# BrimEff.net
KiCad netlist of a schematic drawn in EAGLE
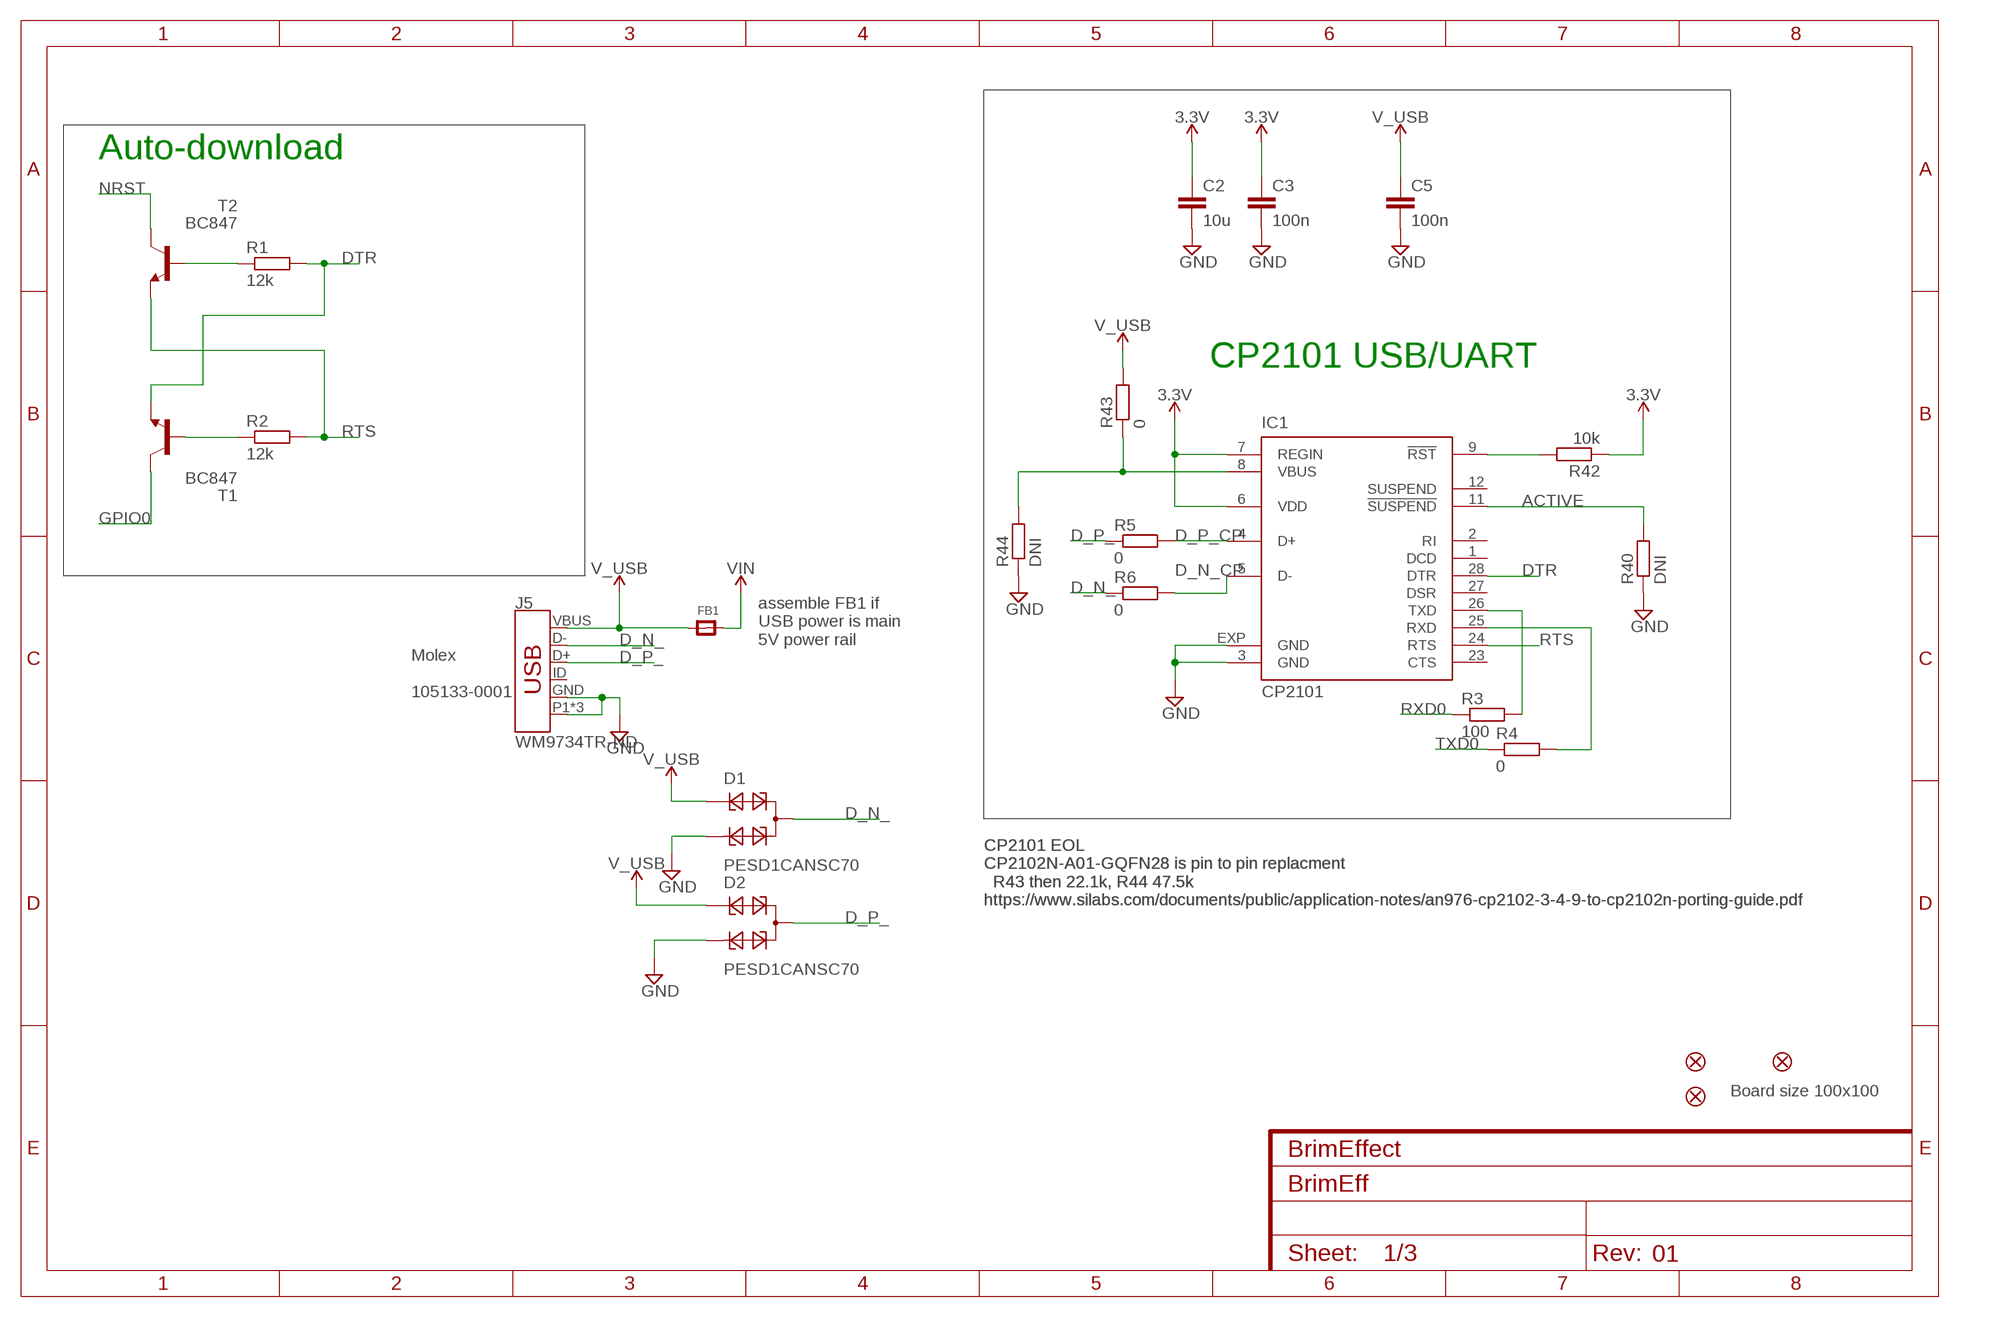
[diagram p0: schematic, sheet 1]
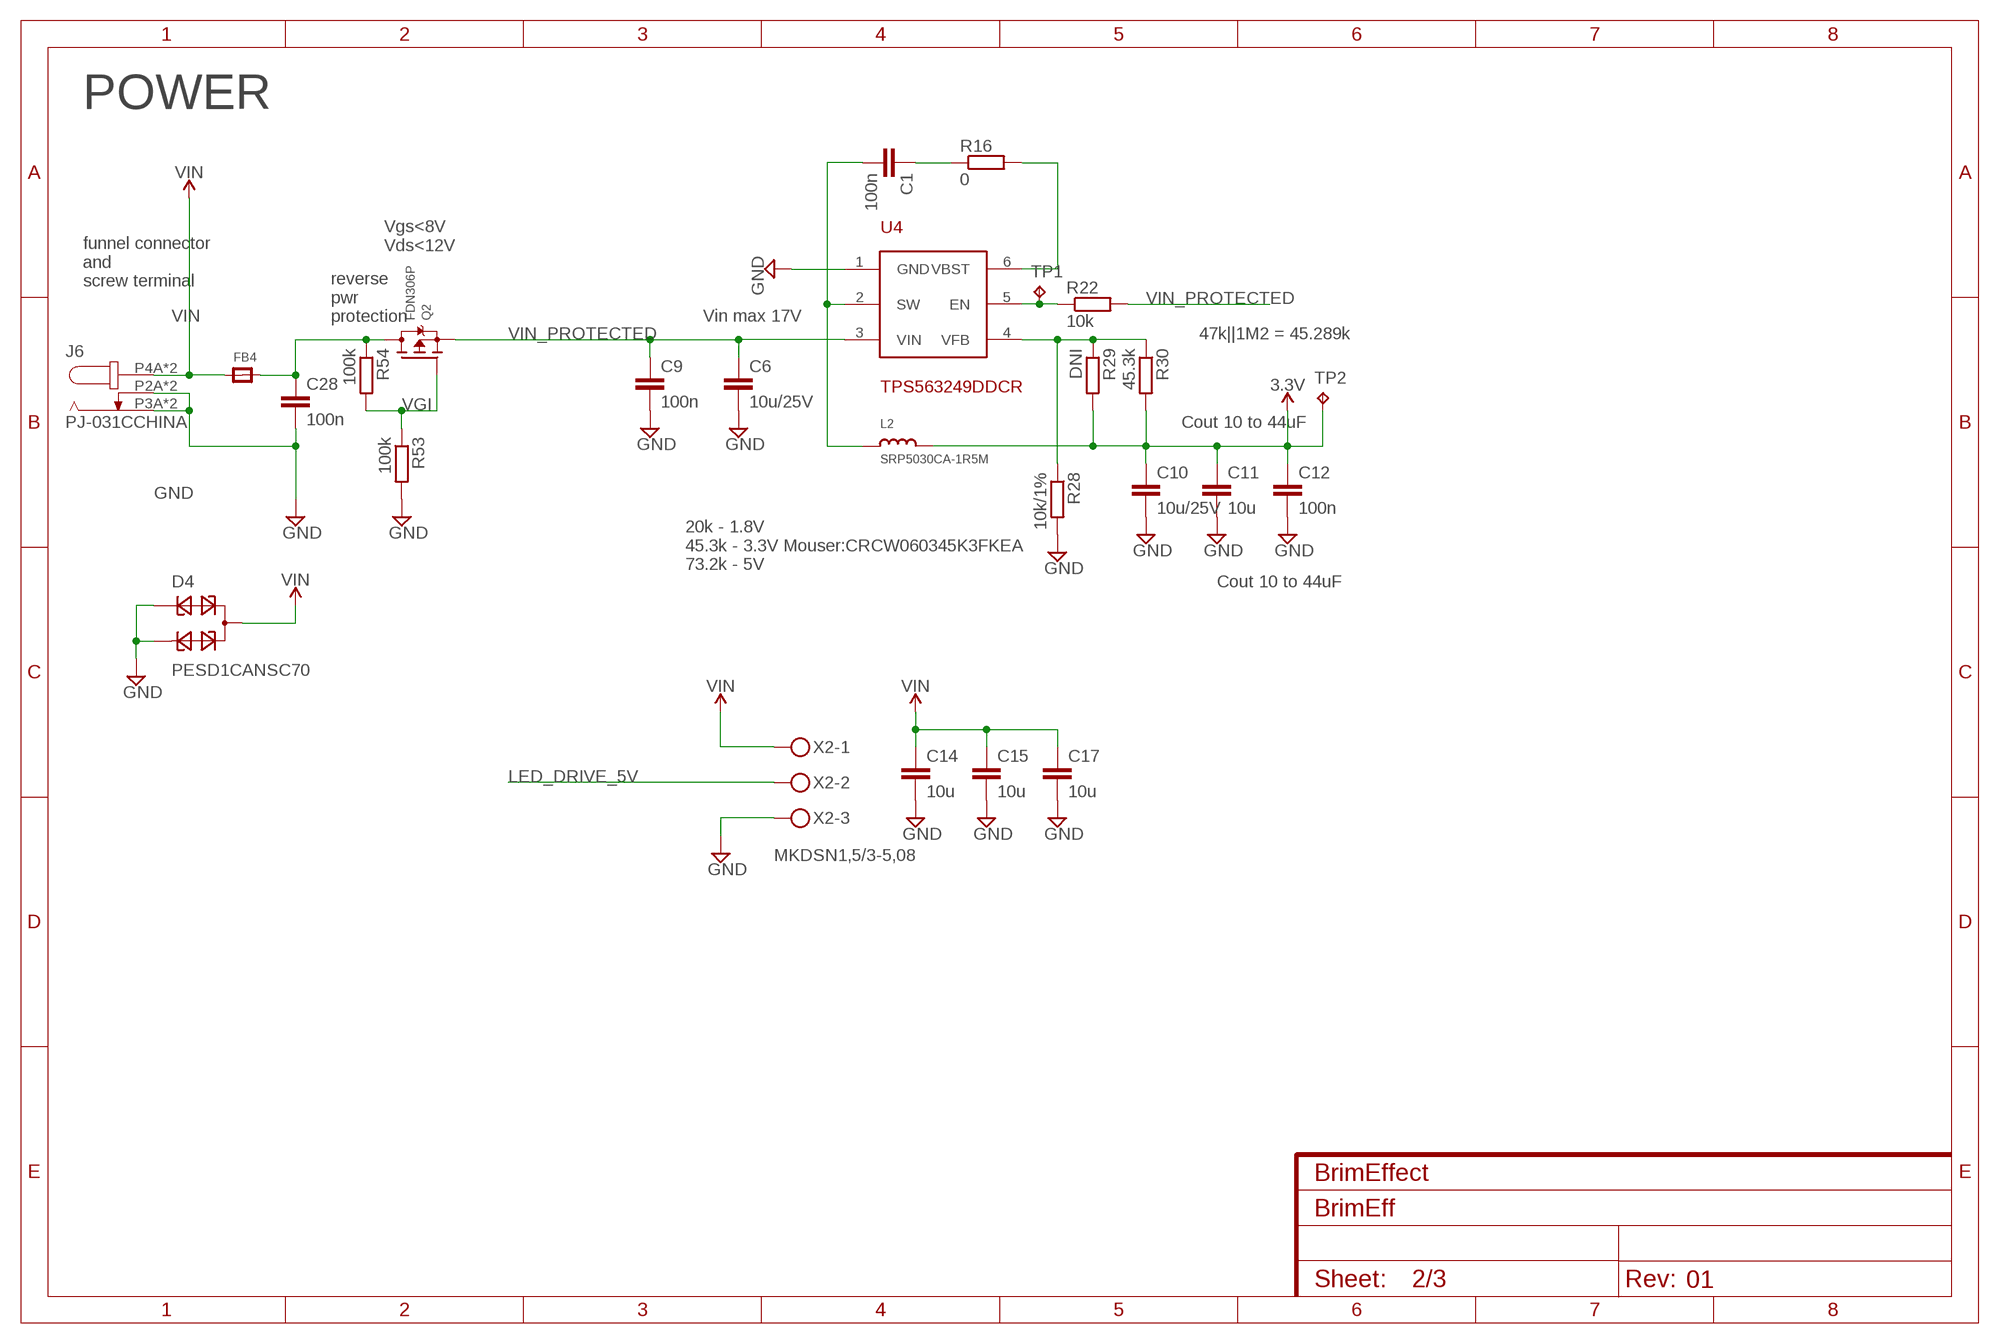
[diagram p1: schematic, sheet 2]
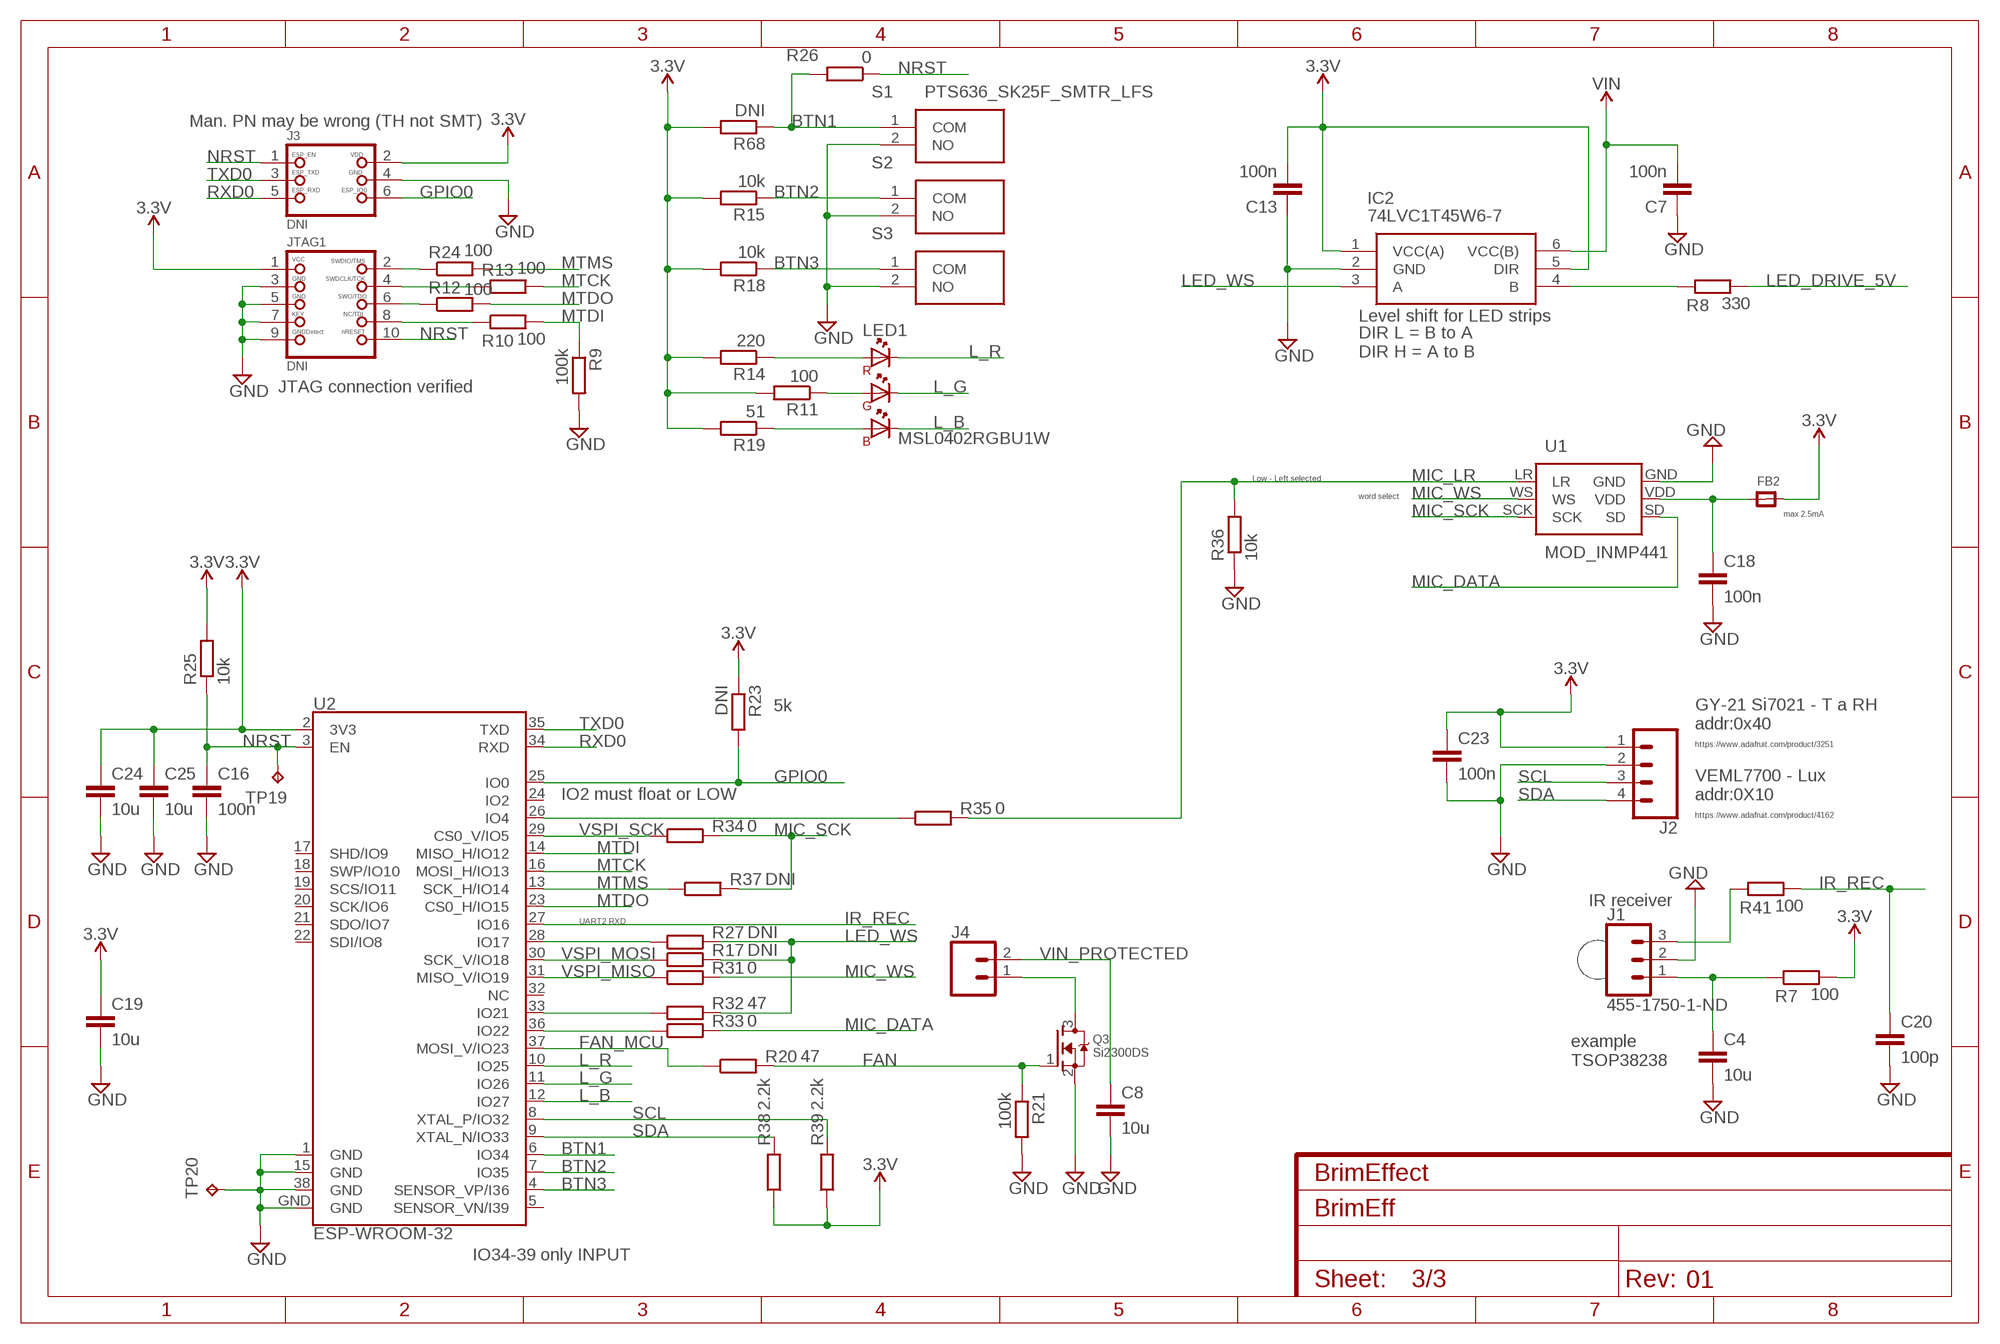
[diagram p2: schematic, sheet 3]

(export (version "E")
  (design (tool "Eeschema 10.0.6"))
  (components
    (comp (ref "C1")
      (value "100n")
      (footprint "eagle-import:C0603K")
      (fields (field (name "PARTNO") "CC0603KRX7R8BB104"))
      (libsource (lib "eagle-import") (part "C-EUC0603K"))
    )
    (comp (ref "C6")
      (value "10u/25V")
      (footprint "eagle-import:C0603K")
      (fields (field (name "PARTNO") "GRM188R61E106KA73J"))
      (libsource (lib "eagle-import") (part "C-EUC0603K"))
    )
    (comp (ref "C9")
      (value "100n")
      (footprint "eagle-import:C0603K")
      (fields (field (name "PARTNO") "CC0603KRX7R8BB104"))
      (libsource (lib "eagle-import") (part "C-EUC0603K"))
    )
    (comp (ref "C10")
      (value "10u/25V")
      (footprint "eagle-import:C0603K")
      (fields (field (name "PARTNO") "GRM188R61E106KA73J"))
      (libsource (lib "eagle-import") (part "C-EUC0603K"))
    )
    (comp (ref "C11")
      (value "10u")
      (footprint "eagle-import:C0603K")
      (fields (field (name "PARTNO") "GRM188R61A106KE69J"))
      (libsource (lib "eagle-import") (part "C-EUC0603K"))
    )
    (comp (ref "C12")
      (value "100n")
      (footprint "eagle-import:C0603K")
      (fields (field (name "PARTNO") "CC0603KRX7R8BB104"))
      (libsource (lib "eagle-import") (part "C-EUC0603K"))
    )
    (comp (ref "C14")
      (value "10u")
      (footprint "eagle-import:C0603K")
      (fields (field (name "PARTNO") "GRM188R61A106KE69J"))
      (libsource (lib "eagle-import") (part "C-EUC0603K"))
    )
    (comp (ref "C15")
      (value "10u")
      (footprint "eagle-import:C0603K")
      (fields (field (name "PARTNO") "GRM188R61A106KE69J"))
      (libsource (lib "eagle-import") (part "C-EUC0603K"))
    )
    (comp (ref "C17")
      (value "10u")
      (footprint "eagle-import:C0603K")
      (fields (field (name "PARTNO") "GRM188R61A106KE69J"))
      (libsource (lib "eagle-import") (part "C-EUC0603K"))
    )
    (comp (ref "C28")
      (value "100n")
      (footprint "eagle-import:C0603K")
      (fields (field (name "PARTNO") "CC0603KRX7R8BB104"))
      (libsource (lib "eagle-import") (part "C-EUC0603K"))
    )
    (comp (ref "D4")
      (value "PESD1CANSC70")
      (footprint "eagle-import:SOT323-R")
      (fields (field (name "PARTNO") "PESD1CAN-UX"))
      (libsource (lib "eagle-import") (part "PESD1CANSC70"))
    )
    (comp (ref "FB4")
      (value "FERRITE")
      (footprint "eagle-import:0603")
      (fields (field (name "PARTNO") "BLM18PG121SN1D"))
      (libsource (lib "eagle-import") (part "FERRITE"))
    )
    (comp (ref "J6")
      (value "PJ-031CCHINA")
      (footprint "eagle-import:DC-005_5.5X2.1MM_JACK")
      (libsource (lib "eagle-import") (part "PJ-031CCHINA"))
    )
    (comp (ref "L2")
      (value "SRP5030CA-1R5M")
      (footprint "eagle-import:SRP5030CA")
      (fields (field (name "PARTNO") "SRP5030CA-1R5M "))
      (libsource (lib "eagle-import") (part "SRP5030CA-1R5M"))
    )
    (comp (ref "Q2")
      (value "FDN306P")
      (footprint "eagle-import:SOT23-WIDE")
      (libsource (lib "eagle-import") (part "MOSFET-PWIDE"))
    )
    (comp (ref "R16")
      (value "0")
      (footprint "eagle-import:R0603")
      (fields (field (name "PARTNO") "CRCW06030000Z0EAC"))
      (libsource (lib "eagle-import") (part "R-EU_R0603"))
    )
    (comp (ref "R22")
      (value "10k")
      (footprint "eagle-import:R0603")
      (fields (field (name "PARTNO") "CRCW060310K0JNEAC"))
      (libsource (lib "eagle-import") (part "R-EU_R0603"))
    )
    (comp (ref "R28")
      (value "10k/1%")
      (footprint "eagle-import:R0603")
      (fields (field (name "PARTNO") "RN73R1JTTD1002D25"))
      (libsource (lib "eagle-import") (part "R-EU_R0603"))
    )
    (comp (ref "R29")
      (value "DNI")
      (footprint "eagle-import:R0603")
      (libsource (lib "eagle-import") (part "R-EU_R0603"))
    )
    (comp (ref "R30")
      (value "45.3k")
      (footprint "eagle-import:R0603")
      (fields (field (name "PARTNO") "ERJ-PB3D4532V"))
      (libsource (lib "eagle-import") (part "R-EU_R0603"))
    )
    (comp (ref "R53")
      (value "100k")
      (footprint "eagle-import:R0603")
      (fields (field (name "PARTNO") "CRCW0603100KFKEAC"))
      (libsource (lib "eagle-import") (part "R-EU_R0603"))
    )
    (comp (ref "R54")
      (value "100k")
      (footprint "eagle-import:R0603")
      (fields (field (name "PARTNO") "CRCW0603100KFKEAC"))
      (libsource (lib "eagle-import") (part "R-EU_R0603"))
    )
    (comp (ref "TP1")
      (value "TPTP10R")
      (footprint "eagle-import:TP10R")
      (libsource (lib "eagle-import") (part "TPTP10R"))
    )
    (comp (ref "TP2")
      (value "TPTP10R")
      (footprint "eagle-import:TP10R")
      (libsource (lib "eagle-import") (part "TPTP10R"))
    )
    (comp (ref "U4")
      (value "TPS563249DDCR")
      (footprint "eagle-import:SOT23-6")
      (fields (field (name "PARTNO") "TPS563249DDCR "))
      (libsource (lib "eagle-import") (part "TPS5632149DDCR"))
    )
    (comp (ref "X2")
      (value "MKDSN1,5/3-5,08")
      (footprint "eagle-import:MKDSN1,5_3-5,08")
      (libsource (lib "eagle-import") (part "MKDSN1,5/3-5,08"))
    )
    (comp (ref "C4")
      (value "10u")
      (footprint "eagle-import:C0603K")
      (fields (field (name "PARTNO") "GRM188R61A106KE69J"))
      (libsource (lib "eagle-import") (part "C-EUC0603K"))
    )
    (comp (ref "C7")
      (value "100n")
      (footprint "eagle-import:C0603K")
      (fields (field (name "PARTNO") "CC0603KRX7R8BB104"))
      (libsource (lib "eagle-import") (part "C-EUC0603K"))
    )
    (comp (ref "C8")
      (value "10u")
      (footprint "eagle-import:C0603K")
      (fields (field (name "PARTNO") "GRM188R61A106KE69J"))
      (libsource (lib "eagle-import") (part "C-EUC0603K"))
    )
    (comp (ref "C13")
      (value "100n")
      (footprint "eagle-import:C0603K")
      (fields (field (name "PARTNO") "CC0603KRX7R8BB104"))
      (libsource (lib "eagle-import") (part "C-EUC0603K"))
    )
    (comp (ref "C16")
      (value "100n")
      (footprint "eagle-import:C0603K")
      (fields (field (name "PARTNO") "CC0603KRX7R8BB104"))
      (libsource (lib "eagle-import") (part "C-EUC0603K"))
    )
    (comp (ref "C18")
      (value "100n")
      (footprint "eagle-import:C0603K")
      (fields (field (name "PARTNO") "CC0603KRX7R8BB104"))
      (libsource (lib "eagle-import") (part "C-EUC0603K"))
    )
    (comp (ref "C19")
      (value "10u")
      (footprint "eagle-import:C0603K")
      (fields (field (name "PARTNO") "GRM188R61A106KE69J"))
      (libsource (lib "eagle-import") (part "C-EUC0603K"))
    )
    (comp (ref "C20")
      (value "100p")
      (footprint "eagle-import:C0603K")
      (fields (field (name "PARTNO") "GRM188R61A106KE69J"))
      (libsource (lib "eagle-import") (part "C-EUC0603K"))
    )
    (comp (ref "C23")
      (value "100n")
      (footprint "eagle-import:C0603K")
      (fields (field (name "PARTNO") "CC0603KRX7R8BB104"))
      (libsource (lib "eagle-import") (part "C-EUC0603K"))
    )
    (comp (ref "C24")
      (value "10u")
      (footprint "eagle-import:C0603K")
      (fields (field (name "PARTNO") "GRM188R61A106KE69J"))
      (libsource (lib "eagle-import") (part "C-EUC0603K"))
    )
    (comp (ref "C25")
      (value "10u")
      (footprint "eagle-import:C0603K")
      (fields (field (name "PARTNO") "GRM188R61A106KE69J"))
      (libsource (lib "eagle-import") (part "C-EUC0603K"))
    )
    (comp (ref "FB2")
      (value "FERRITE")
      (footprint "eagle-import:0603")
      (fields (field (name "PARTNO") "BLM18PG121SN1D"))
      (libsource (lib "eagle-import") (part "FERRITE"))
    )
    (comp (ref "IC2")
      (value "74LVC1T45W6-7")
      (footprint "eagle-import:SOT95P285X140-6N")
      (fields (field (name "MOUSER_PART_NUMBER") "621-74LVC1T45W6-7"))
      (libsource (lib "eagle-import") (part "74LVC1T45W6-7"))
    )
    (comp (ref "J1")
      (value "455-1750-1-ND")
      (footprint "eagle-import:1X03")
      (libsource (lib "eagle-import") (part "CONN_03"))
    )
    (comp (ref "J2")
      (value "CONN_04PTH")
      (footprint "eagle-import:1X04")
      (libsource (lib "eagle-import") (part "CONN_04PTH"))
    )
    (comp (ref "J3")
      (value "DNI")
      (footprint "eagle-import:2X03_1.27MM_SMT")
      (fields (field (name "PARTNO") "HTMS-103-03-T-D-SM"))
      (libsource (lib "eagle-import") (part "HEADER_3X6P_ESPPROG"))
    )
    (comp (ref "J4")
      (value "CONN_02")
      (footprint "eagle-import:1X02")
      (libsource (lib "eagle-import") (part "CONN_02"))
    )
    (comp (ref "JTAG1")
      (value "DNI")
      (footprint "eagle-import:2X05_1.27MM_SMT")
      (fields (field (name "PARTNO") "M50-3600542R"))
      (libsource (lib "eagle-import") (part "JTAG-CORTEXM3"))
    )
    (comp (ref "LED1")
      (value "MSL0402RGBU1W")
      (footprint "eagle-import:MSL0402RGBU1-W")
      (libsource (lib "eagle-import") (part "MSL0402RGBU1W"))
    )
    (comp (ref "Q3")
      (value "Si2300DS")
      (footprint "eagle-import:SOT23")
      (fields (field (name "PARTNO") "SI2300DS-T1-GE3"))
      (libsource (lib "eagle-import") (part "MOSFET-NREFLOW"))
    )
    (comp (ref "R7")
      (value "100")
      (footprint "eagle-import:R0603")
      (fields (field (name "PARTNO") "CRCW0603100RFKEAC"))
      (libsource (lib "eagle-import") (part "R-EU_R0603"))
    )
    (comp (ref "R8")
      (value "330")
      (footprint "eagle-import:R0603")
      (fields (field (name "PARTNO") "CRCW0603100RFKEAC"))
      (libsource (lib "eagle-import") (part "R-EU_R0603"))
    )
    (comp (ref "R9")
      (value "100k")
      (footprint "eagle-import:R0603")
      (fields (field (name "PARTNO") "CRCW0603100KFKEAC"))
      (libsource (lib "eagle-import") (part "R-EU_R0603"))
    )
    (comp (ref "R10")
      (value "100")
      (footprint "eagle-import:R0603")
      (fields (field (name "PARTNO") "CRCW0603100RFKEAC"))
      (libsource (lib "eagle-import") (part "R-EU_R0603"))
    )
    (comp (ref "R11")
      (value "100")
      (footprint "eagle-import:R0603")
      (fields (field (name "PARTNO") "CRCW0603100RFKEAC"))
      (libsource (lib "eagle-import") (part "R-EU_R0603"))
    )
    (comp (ref "R12")
      (value "100")
      (footprint "eagle-import:R0603")
      (fields (field (name "PARTNO") "CRCW0603100RFKEAC"))
      (libsource (lib "eagle-import") (part "R-EU_R0603"))
    )
    (comp (ref "R13")
      (value "100")
      (footprint "eagle-import:R0603")
      (fields (field (name "PARTNO") "CRCW0603100RFKEAC"))
      (libsource (lib "eagle-import") (part "R-EU_R0603"))
    )
    (comp (ref "R14")
      (value "220")
      (footprint "eagle-import:R0603")
      (fields (field (name "PARTNO") "CRCW0603100RFKEAC"))
      (libsource (lib "eagle-import") (part "R-EU_R0603"))
    )
    (comp (ref "R15")
      (value "10k")
      (footprint "eagle-import:R0603")
      (fields (field (name "PARTNO") "CRCW060310K0JNEAC"))
      (libsource (lib "eagle-import") (part "R-EU_R0603"))
    )
    (comp (ref "R17")
      (value "DNI")
      (footprint "eagle-import:R0603")
      (fields (field (name "PARTNO") "CRCW060347R0FKEAC"))
      (libsource (lib "eagle-import") (part "R-EU_R0603"))
    )
    (comp (ref "R18")
      (value "10k")
      (footprint "eagle-import:R0603")
      (fields (field (name "PARTNO") "CRCW060310K0JNEAC"))
      (libsource (lib "eagle-import") (part "R-EU_R0603"))
    )
    (comp (ref "R19")
      (value "51")
      (footprint "eagle-import:R0603")
      (fields (field (name "PARTNO") "CRCW0603100RFKEAC"))
      (libsource (lib "eagle-import") (part "R-EU_R0603"))
    )
    (comp (ref "R20")
      (value "47")
      (footprint "eagle-import:R0603")
      (fields (field (name "PARTNO") "CRCW060347R0FKEAC"))
      (libsource (lib "eagle-import") (part "R-EU_R0603"))
    )
    (comp (ref "R21")
      (value "100k")
      (footprint "eagle-import:R0603")
      (fields (field (name "PARTNO") "CRCW0603100KFKEAC"))
      (libsource (lib "eagle-import") (part "R-EU_R0603"))
    )
    (comp (ref "R23")
      (value "DNI")
      (footprint "eagle-import:R0603")
      (fields (field (name "PARTNO") "CRCW06030000Z0EAC"))
      (libsource (lib "eagle-import") (part "R-EU_R0603"))
    )
    (comp (ref "R24")
      (value "100")
      (footprint "eagle-import:R0603")
      (fields (field (name "PARTNO") "CRCW0603100RFKEAC"))
      (libsource (lib "eagle-import") (part "R-EU_R0603"))
    )
    (comp (ref "R25")
      (value "10k")
      (footprint "eagle-import:R0603")
      (fields (field (name "PARTNO") "CRCW060310K0JNEAC"))
      (libsource (lib "eagle-import") (part "R-EU_R0603"))
    )
    (comp (ref "R26")
      (value "0")
      (footprint "eagle-import:R0603")
      (fields (field (name "PARTNO") "CRCW060310K0JNEAC"))
      (libsource (lib "eagle-import") (part "R-EU_R0603"))
    )
    (comp (ref "R27")
      (value "DNI")
      (footprint "eagle-import:R0603")
      (fields (field (name "PARTNO") "CRCW060347R0FKEAC"))
      (libsource (lib "eagle-import") (part "R-EU_R0603"))
    )
    (comp (ref "R31")
      (value "0")
      (footprint "eagle-import:R0603")
      (fields (field (name "PARTNO") "CRCW060347R0FKEAC"))
      (libsource (lib "eagle-import") (part "R-EU_R0603"))
    )
    (comp (ref "R32")
      (value "47")
      (footprint "eagle-import:R0603")
      (fields (field (name "PARTNO") "CRCW060347R0FKEAC"))
      (libsource (lib "eagle-import") (part "R-EU_R0603"))
    )
    (comp (ref "R33")
      (value "0")
      (footprint "eagle-import:R0603")
      (fields (field (name "PARTNO") "CRCW060347R0FKEAC"))
      (libsource (lib "eagle-import") (part "R-EU_R0603"))
    )
    (comp (ref "R34")
      (value "0")
      (footprint "eagle-import:R0603")
      (fields (field (name "PARTNO") "CRCW060347R0FKEAC"))
      (libsource (lib "eagle-import") (part "R-EU_R0603"))
    )
    (comp (ref "R35")
      (value "0")
      (footprint "eagle-import:R0603")
      (fields (field (name "PARTNO") "CRCW060347R0FKEAC"))
      (libsource (lib "eagle-import") (part "R-EU_R0603"))
    )
    (comp (ref "R36")
      (value "10k")
      (footprint "eagle-import:R0603")
      (fields (field (name "PARTNO") "CRCW060310K0JNEAC"))
      (libsource (lib "eagle-import") (part "R-EU_R0603"))
    )
    (comp (ref "R37")
      (value "DNI")
      (footprint "eagle-import:R0603")
      (fields (field (name "PARTNO") "CRCW060347R0FKEAC"))
      (libsource (lib "eagle-import") (part "R-EU_R0603"))
    )
    (comp (ref "R38")
      (value "2.2k")
      (footprint "eagle-import:R0603")
      (fields (field (name "PARTNO") "CRCW060347R0FKEAC"))
      (libsource (lib "eagle-import") (part "R-EU_R0603"))
    )
    (comp (ref "R39")
      (value "2.2k")
      (footprint "eagle-import:R0603")
      (fields (field (name "PARTNO") "CRCW060347R0FKEAC"))
      (libsource (lib "eagle-import") (part "R-EU_R0603"))
    )
    (comp (ref "R41")
      (value "100")
      (footprint "eagle-import:R0603")
      (fields (field (name "PARTNO") "CRCW0603100RFKEAC"))
      (libsource (lib "eagle-import") (part "R-EU_R0603"))
    )
    (comp (ref "R68")
      (value "DNI")
      (footprint "eagle-import:R0603")
      (fields (field (name "PARTNO") "CRCW060310K0JNEAC"))
      (libsource (lib "eagle-import") (part "R-EU_R0603"))
    )
    (comp (ref "S1")
      (value "PTS636_SK25F_SMTR_LFS")
      (footprint "eagle-import:PTS636SK25FSMTRLFS")
      (fields
        (field (name "MANUFACTURER_PART_NUMBER") "PTS636 SK25F SMTR LFS")
        (field (name "MOUSER_PART_NUMBER") "611-PTS636SK25FSMTRL")
      )
      (libsource (lib "eagle-import") (part "PTS636_SK25F_SMTR_LFS"))
    )
    (comp (ref "S2")
      (value "PTS636_SK25F_SMTR_LFS")
      (footprint "eagle-import:PTS636SK25FSMTRLFS")
      (fields
        (field (name "MANUFACTURER_PART_NUMBER") "PTS636 SK25F SMTR LFS")
        (field (name "MOUSER_PART_NUMBER") "611-PTS636SK25FSMTRL")
      )
      (libsource (lib "eagle-import") (part "PTS636_SK25F_SMTR_LFS"))
    )
    (comp (ref "S3")
      (value "PTS636_SK25F_SMTR_LFS")
      (footprint "eagle-import:PTS636SK25FSMTRLFS")
      (fields
        (field (name "MANUFACTURER_PART_NUMBER") "PTS636 SK25F SMTR LFS")
        (field (name "MOUSER_PART_NUMBER") "611-PTS636SK25FSMTRL")
      )
      (libsource (lib "eagle-import") (part "PTS636_SK25F_SMTR_LFS"))
    )
    (comp (ref "TP19")
      (value "TPTP10R")
      (footprint "eagle-import:TP10R")
      (libsource (lib "eagle-import") (part "TPTP10R"))
    )
    (comp (ref "TP20")
      (value "TPTP10R")
      (footprint "eagle-import:TP10R")
      (libsource (lib "eagle-import") (part "TPTP10R"))
    )
    (comp (ref "U1")
      (value "MOD_INMP441")
      (footprint "eagle-import:MOD_INMP441")
      (libsource (lib "eagle-import") (part "MOD_INMP441"))
    )
    (comp (ref "U2")
      (value "ESP-WROOM-32")
      (footprint "eagle-import:ESP-WROOM-32")
      (fields (field (name "PARTNO") "ESP32-WROOM-32"))
      (libsource (lib "eagle-import") (part "ESP-WROOM-32"))
    )
    (comp (ref "C2")
      (value "10u")
      (footprint "eagle-import:C0603K")
      (fields (field (name "PARTNO") "GRM188R61A106KE69J"))
      (libsource (lib "eagle-import") (part "C-EUC0603K"))
    )
    (comp (ref "C3")
      (value "100n")
      (footprint "eagle-import:C0603K")
      (fields (field (name "PARTNO") "CC0603KRX7R8BB104"))
      (libsource (lib "eagle-import") (part "C-EUC0603K"))
    )
    (comp (ref "C5")
      (value "100n")
      (footprint "eagle-import:C0603K")
      (fields (field (name "PARTNO") "CC0603KRX7R8BB104"))
      (libsource (lib "eagle-import") (part "C-EUC0603K"))
    )
    (comp (ref "D1")
      (value "PESD1CANSC70")
      (footprint "eagle-import:SOT323-R")
      (fields (field (name "PARTNO") "PESD1CAN-UX"))
      (libsource (lib "eagle-import") (part "PESD1CANSC70"))
    )
    (comp (ref "D2")
      (value "PESD1CANSC70")
      (footprint "eagle-import:SOT323-R")
      (fields (field (name "PARTNO") "PESD1CAN-UX"))
      (libsource (lib "eagle-import") (part "PESD1CANSC70"))
    )
    (comp (ref "FB1")
      (value "FERRITE")
      (footprint "eagle-import:0603")
      (fields (field (name "PARTNO") "BLM18PG121SN1D"))
      (libsource (lib "eagle-import") (part "FERRITE"))
    )
    (comp (ref "FID1")
      (value "FIDUCIAL\"\"")
      (footprint "eagle-import:FIDUCIAL_1MM")
      (libsource (lib "eagle-import") (part "FIDUCIAL{dblquote}{dblquote}"))
    )
    (comp (ref "FID2")
      (value "FIDUCIAL\"\"")
      (footprint "eagle-import:FIDUCIAL_1MM")
      (libsource (lib "eagle-import") (part "FIDUCIAL{dblquote}{dblquote}"))
    )
    (comp (ref "FID4")
      (value "FIDUCIAL\"\"")
      (footprint "eagle-import:FIDUCIAL_1MM")
      (libsource (lib "eagle-import") (part "FIDUCIAL{dblquote}{dblquote}"))
    )
    (comp (ref "IC1")
      (value "CP2101")
      (footprint "eagle-import:MLP28")
      (fields (field (name "PARTNO") "CP2101-GM"))
      (libsource (lib "eagle-import") (part "CP210X_USB_UART"))
    )
    (comp (ref "J5")
      (value "WM9734TR-ND")
      (footprint "eagle-import:USB-B-MICRO-SMD_VERT")
      (fields (field (name "PARTNO") "105133-0001"))
      (libsource (lib "eagle-import") (part "USB_MICRO-B_FEMALE-SMT-VERT"))
    )
    (comp (ref "R1")
      (value "12k")
      (footprint "eagle-import:R0603")
      (fields (field (name "PARTNO") "RC0603FR-0712KL"))
      (libsource (lib "eagle-import") (part "R-EU_R0603"))
    )
    (comp (ref "R2")
      (value "12k")
      (footprint "eagle-import:R0603")
      (fields (field (name "PARTNO") "RC0603FR-0712KL"))
      (libsource (lib "eagle-import") (part "R-EU_R0603"))
    )
    (comp (ref "R3")
      (value "100")
      (footprint "eagle-import:R0603")
      (fields (field (name "PARTNO") "CRCW0603100RFKEAC"))
      (libsource (lib "eagle-import") (part "R-EU_R0603"))
    )
    (comp (ref "R4")
      (value "0")
      (footprint "eagle-import:R0603")
      (fields (field (name "PARTNO") "CRCW06030000Z0EAC"))
      (libsource (lib "eagle-import") (part "R-EU_R0603"))
    )
    (comp (ref "R5")
      (value "0")
      (footprint "eagle-import:R0603")
      (fields (field (name "PARTNO") "CRCW06030000Z0EAC"))
      (libsource (lib "eagle-import") (part "R-EU_R0603"))
    )
    (comp (ref "R6")
      (value "0")
      (footprint "eagle-import:R0603")
      (fields (field (name "PARTNO") "CRCW06030000Z0EAC"))
      (libsource (lib "eagle-import") (part "R-EU_R0603"))
    )
    (comp (ref "R40")
      (value "DNI")
      (footprint "eagle-import:R0603")
      (fields (field (name "PARTNO") "CRCW06030000Z0EAC"))
      (libsource (lib "eagle-import") (part "R-EU_R0603"))
    )
    (comp (ref "R42")
      (value "10k")
      (footprint "eagle-import:R0603")
      (fields (field (name "PARTNO") "CRCW060310K0JNEAC"))
      (libsource (lib "eagle-import") (part "R-EU_R0603"))
    )
    (comp (ref "R43")
      (value "0")
      (footprint "eagle-import:R0603")
      (fields (field (name "PARTNO") "CRCW06030000Z0EAC"))
      (libsource (lib "eagle-import") (part "R-EU_R0603"))
    )
    (comp (ref "R44")
      (value "DNI")
      (footprint "eagle-import:R0603")
      (fields (field (name "PARTNO") "CRCW06030000Z0EAC"))
      (libsource (lib "eagle-import") (part "R-EU_R0603"))
    )
    (comp (ref "T1")
      (value "BC847")
      (footprint "eagle-import:SOT23")
      (fields (field (name "PARTNO") "BC847A-TP"))
      (libsource (lib "eagle-import") (part "BC847"))
    )
    (comp (ref "T2")
      (value "BC847")
      (footprint "eagle-import:SOT23")
      (fields (field (name "PARTNO") "BC847A-TP"))
      (libsource (lib "eagle-import") (part "BC847"))
    )
  )
  (nets
    (net (code "1") (name "3.3V") (class "Default")
      (node (ref "C10") (pin "1") (pinfunction "1_1") (pintype "passive"))
      (node (ref "C11") (pin "1") (pinfunction "1_1") (pintype "passive"))
      (node (ref "C12") (pin "1") (pinfunction "1_1") (pintype "passive"))
      (node (ref "C13") (pin "2") (pinfunction "2_2") (pintype "passive"))
      (node (ref "C19") (pin "1") (pinfunction "1_1") (pintype "passive"))
      (node (ref "C2") (pin "1") (pinfunction "1_1") (pintype "passive"))
      (node (ref "C23") (pin "1") (pinfunction "1_1") (pintype "passive"))
      (node (ref "C24") (pin "1") (pinfunction "1_1") (pintype "passive"))
      (node (ref "C25") (pin "1") (pinfunction "1_1") (pintype "passive"))
      (node (ref "C3") (pin "1") (pinfunction "1_1") (pintype "passive"))
      (node (ref "FB2") (pin "2") (pinfunction "P$2_2") (pintype "passive"))
      (node (ref "IC1") (pin "6") (pinfunction "VDD_6") (pintype "power_in"))
      (node (ref "IC1") (pin "7") (pinfunction "REGIN_7") (pintype "passive"))
      (node (ref "IC2") (pin "1") (pinfunction "VCC(A)_1") (pintype "bidirectional"))
      (node (ref "IC2") (pin "5") (pinfunction "DIR_5") (pintype "bidirectional"))
      (node (ref "J2") (pin "1") (pinfunction "1_1") (pintype "passive"))
      (node (ref "J3") (pin "2") (pinfunction "2_2") (pintype "passive"))
      (node (ref "JTAG1") (pin "1") (pinfunction "1_1") (pintype "passive"))
      (node (ref "L2") (pin "P$2") (pinfunction "2_P$2") (pintype "passive"))
      (node (ref "R11") (pin "2") (pinfunction "2_2") (pintype "passive"))
      (node (ref "R14") (pin "2") (pinfunction "2_2") (pintype "passive"))
      (node (ref "R15") (pin "2") (pinfunction "2_2") (pintype "passive"))
      (node (ref "R18") (pin "2") (pinfunction "2_2") (pintype "passive"))
      (node (ref "R19") (pin "2") (pinfunction "2_2") (pintype "passive"))
      (node (ref "R23") (pin "1") (pinfunction "1_1") (pintype "passive"))
      (node (ref "R25") (pin "2") (pinfunction "2_2") (pintype "passive"))
      (node (ref "R29") (pin "2") (pinfunction "2_2") (pintype "passive"))
      (node (ref "R30") (pin "2") (pinfunction "2_2") (pintype "passive"))
      (node (ref "R38") (pin "1") (pinfunction "1_1") (pintype "passive"))
      (node (ref "R39") (pin "1") (pinfunction "1_1") (pintype "passive"))
      (node (ref "R42") (pin "1") (pinfunction "1_1") (pintype "passive"))
      (node (ref "R68") (pin "2") (pinfunction "2_2") (pintype "passive"))
      (node (ref "R7") (pin "2") (pinfunction "2_2") (pintype "passive"))
      (node (ref "TP2") (pin "TP") (pinfunction "TP_TP") (pintype "input"))
      (node (ref "U2") (pin "2") (pinfunction "3V3_2") (pintype "bidirectional"))
    )
    (net (code "2") (name "ACTIVE") (class "Default")
      (node (ref "IC1") (pin "11") (pinfunction "~{SUSPEND}_11") (pintype "output"))
      (node (ref "R40") (pin "2") (pinfunction "2_2") (pintype "passive"))
    )
    (net (code "3") (name "BTN1") (class "Default")
      (node (ref "R26") (pin "2") (pinfunction "2_2") (pintype "passive"))
      (node (ref "R68") (pin "1") (pinfunction "1_1") (pintype "passive"))
      (node (ref "S1") (pin "1") (pinfunction "COM_1") (pintype "bidirectional"))
      (node (ref "U2") (pin "6") (pinfunction "IO34_6") (pintype "bidirectional"))
    )
    (net (code "4") (name "BTN2") (class "Default")
      (node (ref "R15") (pin "1") (pinfunction "1_1") (pintype "passive"))
      (node (ref "S2") (pin "1") (pinfunction "COM_1") (pintype "bidirectional"))
      (node (ref "U2") (pin "7") (pinfunction "IO35_7") (pintype "bidirectional"))
    )
    (net (code "5") (name "BTN3") (class "Default")
      (node (ref "R18") (pin "1") (pinfunction "1_1") (pintype "passive"))
      (node (ref "S3") (pin "1") (pinfunction "COM_1") (pintype "bidirectional"))
      (node (ref "U2") (pin "4") (pinfunction "SENSOR_VP/I36_4") (pintype "bidirectional"))
    )
    (net (code "6") (name "DTR") (class "Default")
      (node (ref "IC1") (pin "28") (pinfunction "DTR_28") (pintype "output"))
      (node (ref "R1") (pin "2") (pinfunction "2_2") (pintype "passive"))
      (node (ref "T1") (pin "2") (pinfunction "E_2") (pintype "passive"))
    )
    (net (code "7") (name "D_N_") (class "Default")
      (node (ref "D1") (pin "3") (pinfunction "3_3") (pintype "passive"))
      (node (ref "J5") (pin "D-") (pinfunction "D-_D-") (pintype "bidirectional"))
      (node (ref "R6") (pin "1") (pinfunction "1_1") (pintype "passive"))
    )
    (net (code "8") (name "D_N_CP") (class "Default")
      (node (ref "IC1") (pin "5") (pinfunction "D-_5") (pintype "bidirectional"))
      (node (ref "R6") (pin "2") (pinfunction "2_2") (pintype "passive"))
    )
    (net (code "9") (name "D_P_") (class "Default")
      (node (ref "D2") (pin "3") (pinfunction "3_3") (pintype "passive"))
      (node (ref "J5") (pin "D+") (pinfunction "D+_D+") (pintype "bidirectional"))
      (node (ref "R5") (pin "1") (pinfunction "1_1") (pintype "passive"))
    )
    (net (code "10") (name "D_P_CP") (class "Default")
      (node (ref "IC1") (pin "4") (pinfunction "D+_4") (pintype "bidirectional"))
      (node (ref "R5") (pin "2") (pinfunction "2_2") (pintype "passive"))
    )
    (net (code "11") (name "FAN") (class "Default")
      (node (ref "Q3") (pin "1") (pinfunction "G_1") (pintype "bidirectional"))
      (node (ref "R20") (pin "2") (pinfunction "2_2") (pintype "passive"))
      (node (ref "R21") (pin "1") (pinfunction "1_1") (pintype "passive"))
    )
    (net (code "12") (name "FAN_MCU") (class "Default")
      (node (ref "R20") (pin "1") (pinfunction "1_1") (pintype "passive"))
      (node (ref "U2") (pin "37") (pinfunction "MOSI_V/IO23_37") (pintype "bidirectional"))
    )
    (net (code "13") (name "GND") (class "Default")
      (node (ref "C10") (pin "2") (pinfunction "2_2") (pintype "passive"))
      (node (ref "C11") (pin "2") (pinfunction "2_2") (pintype "passive"))
      (node (ref "C12") (pin "2") (pinfunction "2_2") (pintype "passive"))
      (node (ref "C13") (pin "1") (pinfunction "1_1") (pintype "passive"))
      (node (ref "C14") (pin "2") (pinfunction "2_2") (pintype "passive"))
      (node (ref "C15") (pin "2") (pinfunction "2_2") (pintype "passive"))
      (node (ref "C16") (pin "2") (pinfunction "2_2") (pintype "passive"))
      (node (ref "C17") (pin "2") (pinfunction "2_2") (pintype "passive"))
      (node (ref "C18") (pin "2") (pinfunction "2_2") (pintype "passive"))
      (node (ref "C19") (pin "2") (pinfunction "2_2") (pintype "passive"))
      (node (ref "C2") (pin "2") (pinfunction "2_2") (pintype "passive"))
      (node (ref "C20") (pin "2") (pinfunction "2_2") (pintype "passive"))
      (node (ref "C23") (pin "2") (pinfunction "2_2") (pintype "passive"))
      (node (ref "C24") (pin "2") (pinfunction "2_2") (pintype "passive"))
      (node (ref "C25") (pin "2") (pinfunction "2_2") (pintype "passive"))
      (node (ref "C28") (pin "2") (pinfunction "2_2") (pintype "passive"))
      (node (ref "C3") (pin "2") (pinfunction "2_2") (pintype "passive"))
      (node (ref "C4") (pin "2") (pinfunction "2_2") (pintype "passive"))
      (node (ref "C5") (pin "2") (pinfunction "2_2") (pintype "passive"))
      (node (ref "C6") (pin "2") (pinfunction "2_2") (pintype "passive"))
      (node (ref "C7") (pin "1") (pinfunction "1_1") (pintype "passive"))
      (node (ref "C8") (pin "2") (pinfunction "2_2") (pintype "passive"))
      (node (ref "C9") (pin "2") (pinfunction "2_2") (pintype "passive"))
      (node (ref "D1") (pin "2") (pinfunction "2_2") (pintype "passive"))
      (node (ref "D2") (pin "2") (pinfunction "2_2") (pintype "passive"))
      (node (ref "D4") (pin "1") (pinfunction "1_1") (pintype "passive"))
      (node (ref "D4") (pin "2") (pinfunction "2_2") (pintype "passive"))
      (node (ref "IC1") (pin "3") (pinfunction "GND_3") (pintype "power_in"))
      (node (ref "IC1") (pin "EXP") (pinfunction "GND_EXP") (pintype "power_in"))
      (node (ref "IC2") (pin "2") (pinfunction "GND_2") (pintype "bidirectional"))
      (node (ref "J1") (pin "2") (pinfunction "2_2") (pintype "passive"))
      (node (ref "J2") (pin "2") (pinfunction "2_2") (pintype "passive"))
      (node (ref "J3") (pin "4") (pinfunction "4_4") (pintype "passive"))
      (node (ref "J5") (pin "GND") (pinfunction "GND_GND") (pintype "power_in"))
      (node (ref "J5") (pin "P1") (pinfunction "SHIELD_P1") (pintype "bidirectional"))
      (node (ref "J5") (pin "P2") (pinfunction "SHIELD_P2") (pintype "bidirectional"))
      (node (ref "J5") (pin "P3") (pinfunction "SHIELD_P3") (pintype "bidirectional"))
      (node (ref "J6") (pin "P2A") (pinfunction "3_P2A") (pintype "passive"))
      (node (ref "J6") (pin "P2B") (pinfunction "3_P2B") (pintype "passive"))
      (node (ref "J6") (pin "P3A") (pinfunction "2_P3A") (pintype "passive"))
      (node (ref "J6") (pin "P3B") (pinfunction "2_P3B") (pintype "passive"))
      (node (ref "JTAG1") (pin "3") (pinfunction "3_3") (pintype "passive"))
      (node (ref "JTAG1") (pin "5") (pinfunction "5_5") (pintype "passive"))
      (node (ref "JTAG1") (pin "7") (pinfunction "7_7") (pintype "passive"))
      (node (ref "JTAG1") (pin "9") (pinfunction "9_9") (pintype "passive"))
      (node (ref "Q3") (pin "2") (pinfunction "S_2") (pintype "bidirectional"))
      (node (ref "R21") (pin "2") (pinfunction "2_2") (pintype "passive"))
      (node (ref "R28") (pin "2") (pinfunction "2_2") (pintype "passive"))
      (node (ref "R36") (pin "1") (pinfunction "1_1") (pintype "passive"))
      (node (ref "R40") (pin "1") (pinfunction "1_1") (pintype "passive"))
      (node (ref "R44") (pin "1") (pinfunction "1_1") (pintype "passive"))
      (node (ref "R53") (pin "2") (pinfunction "2_2") (pintype "passive"))
      (node (ref "R9") (pin "2") (pinfunction "2_2") (pintype "passive"))
      (node (ref "S1") (pin "2") (pinfunction "NO_2") (pintype "bidirectional"))
      (node (ref "S2") (pin "2") (pinfunction "NO_2") (pintype "bidirectional"))
      (node (ref "S3") (pin "2") (pinfunction "NO_2") (pintype "bidirectional"))
      (node (ref "TP20") (pin "TP") (pinfunction "TP_TP") (pintype "input"))
      (node (ref "U1") (pin "GND") (pinfunction "GND_GND") (pintype "bidirectional"))
      (node (ref "U2") (pin "1") (pinfunction "GND_1") (pintype "bidirectional"))
      (node (ref "U2") (pin "15") (pinfunction "GND_15") (pintype "bidirectional"))
      (node (ref "U2") (pin "38") (pinfunction "GND_38") (pintype "bidirectional"))
      (node (ref "U2") (pin "GND") (pinfunction "GND_GND") (pintype "bidirectional"))
      (node (ref "U4") (pin "1") (pinfunction "GND_1") (pintype "bidirectional"))
      (node (ref "X2") (pin "3") (pinfunction "KL_3") (pintype "passive"))
    )
    (net (code "14") (name "GPIO0") (class "Default")
      (node (ref "J3") (pin "6") (pinfunction "6_6") (pintype "passive"))
      (node (ref "R23") (pin "2") (pinfunction "2_2") (pintype "passive"))
      (node (ref "T1") (pin "3") (pinfunction "C_3") (pintype "passive"))
      (node (ref "U2") (pin "25") (pinfunction "IO0_25") (pintype "bidirectional"))
    )
    (net (code "15") (name "IR_REC") (class "Default")
      (node (ref "C20") (pin "1") (pinfunction "1_1") (pintype "passive"))
      (node (ref "R41") (pin "2") (pinfunction "2_2") (pintype "passive"))
      (node (ref "U2") (pin "27") (pinfunction "IO16_27") (pintype "bidirectional"))
    )
    (net (code "16") (name "LED_DRIVE_5V") (class "Default")
      (node (ref "R8") (pin "2") (pinfunction "2_2") (pintype "passive"))
      (node (ref "X2") (pin "2") (pinfunction "KL_2") (pintype "passive"))
    )
    (net (code "17") (name "LED_WS") (class "Default")
      (node (ref "IC2") (pin "3") (pinfunction "A_3") (pintype "bidirectional"))
      (node (ref "R17") (pin "2") (pinfunction "2_2") (pintype "passive"))
      (node (ref "R27") (pin "2") (pinfunction "2_2") (pintype "passive"))
      (node (ref "R32") (pin "2") (pinfunction "2_2") (pintype "passive"))
    )
    (net (code "18") (name "L_B") (class "Default")
      (node (ref "LED1") (pin "1") (pinfunction "K_B_1") (pintype "passive"))
      (node (ref "U2") (pin "12") (pinfunction "IO27_12") (pintype "bidirectional"))
    )
    (net (code "19") (name "L_G") (class "Default")
      (node (ref "LED1") (pin "2") (pinfunction "K_G_2") (pintype "passive"))
      (node (ref "U2") (pin "11") (pinfunction "IO26_11") (pintype "bidirectional"))
    )
    (net (code "20") (name "L_R") (class "Default")
      (node (ref "LED1") (pin "3") (pinfunction "K_R_3") (pintype "passive"))
      (node (ref "U2") (pin "10") (pinfunction "IO25_10") (pintype "bidirectional"))
    )
    (net (code "21") (name "MIC_DATA") (class "Default")
      (node (ref "R33") (pin "2") (pinfunction "2_2") (pintype "passive"))
      (node (ref "U1") (pin "SD") (pinfunction "SD_SD") (pintype "bidirectional"))
    )
    (net (code "22") (name "MIC_LR") (class "Default")
      (node (ref "R35") (pin "2") (pinfunction "2_2") (pintype "passive"))
      (node (ref "R36") (pin "2") (pinfunction "2_2") (pintype "passive"))
      (node (ref "U1") (pin "LR") (pinfunction "LR_LR") (pintype "bidirectional"))
    )
    (net (code "23") (name "MIC_SCK") (class "Default")
      (node (ref "R34") (pin "2") (pinfunction "2_2") (pintype "passive"))
      (node (ref "R37") (pin "2") (pinfunction "2_2") (pintype "passive"))
      (node (ref "U1") (pin "SCK") (pinfunction "SCK_SCK") (pintype "bidirectional"))
    )
    (net (code "24") (name "MIC_WS") (class "Default")
      (node (ref "R31") (pin "2") (pinfunction "2_2") (pintype "passive"))
      (node (ref "U1") (pin "WS") (pinfunction "WS_WS") (pintype "bidirectional"))
    )
    (net (code "25") (name "MTCK") (class "Default")
      (node (ref "R13") (pin "2") (pinfunction "2_2") (pintype "passive"))
      (node (ref "U2") (pin "16") (pinfunction "MOSI_H/IO13_16") (pintype "bidirectional"))
    )
    (net (code "26") (name "MTDI") (class "Default")
      (node (ref "R10") (pin "2") (pinfunction "2_2") (pintype "passive"))
      (node (ref "R9") (pin "1") (pinfunction "1_1") (pintype "passive"))
      (node (ref "U2") (pin "14") (pinfunction "MISO_H/IO12_14") (pintype "bidirectional"))
    )
    (net (code "27") (name "MTDO") (class "Default")
      (node (ref "R12") (pin "2") (pinfunction "2_2") (pintype "passive"))
      (node (ref "U2") (pin "23") (pinfunction "CS0_H/IO15_23") (pintype "bidirectional"))
    )
    (net (code "28") (name "MTMS") (class "Default")
      (node (ref "R24") (pin "2") (pinfunction "2_2") (pintype "passive"))
      (node (ref "R37") (pin "1") (pinfunction "1_1") (pintype "passive"))
      (node (ref "U2") (pin "13") (pinfunction "SCK_H/IO14_13") (pintype "bidirectional"))
    )
    (net (code "29") (name "NRST") (class "Default")
      (node (ref "C16") (pin "1") (pinfunction "1_1") (pintype "passive"))
      (node (ref "J3") (pin "1") (pinfunction "1_1") (pintype "passive"))
      (node (ref "JTAG1") (pin "10") (pinfunction "10_10") (pintype "passive"))
      (node (ref "R25") (pin "1") (pinfunction "1_1") (pintype "passive"))
      (node (ref "R26") (pin "1") (pinfunction "1_1") (pintype "passive"))
      (node (ref "T2") (pin "3") (pinfunction "C_3") (pintype "passive"))
      (node (ref "TP19") (pin "TP") (pinfunction "TP_TP") (pintype "input"))
      (node (ref "U2") (pin "3") (pinfunction "EN_3") (pintype "bidirectional"))
    )
    (net (code "30") (name "Net-(C1-Pad1)") (class "Default")
      (node (ref "C1") (pin "1") (pinfunction "1_1") (pintype "passive"))
      (node (ref "R16") (pin "1") (pinfunction "1_1") (pintype "passive"))
    )
    (net (code "31") (name "Net-(C4-Pad1)") (class "Default")
      (node (ref "C4") (pin "1") (pinfunction "1_1") (pintype "passive"))
      (node (ref "J1") (pin "1") (pinfunction "1_1") (pintype "passive"))
      (node (ref "R7") (pin "1") (pinfunction "1_1") (pintype "passive"))
    )
    (net (code "32") (name "Net-(FB2-P$1)") (class "Default")
      (node (ref "C18") (pin "1") (pinfunction "1_1") (pintype "passive"))
      (node (ref "FB2") (pin "1") (pinfunction "P$1_1") (pintype "passive"))
      (node (ref "U1") (pin "VDD") (pinfunction "VDD_VDD") (pintype "bidirectional"))
    )
    (net (code "33") (name "Net-(FB4-P$2)") (class "Default")
      (node (ref "C28") (pin "1") (pinfunction "1_1") (pintype "passive"))
      (node (ref "FB4") (pin "2") (pinfunction "P$2_2") (pintype "passive"))
      (node (ref "Q2") (pin "3") (pinfunction "D_3") (pintype "passive"))
      (node (ref "R54") (pin "1") (pinfunction "1_1") (pintype "passive"))
    )
    (net (code "34") (name "Net-(IC1-RXD)") (class "Default")
      (node (ref "IC1") (pin "25") (pinfunction "RXD_25") (pintype "input"))
      (node (ref "R4") (pin "2") (pinfunction "2_2") (pintype "passive"))
    )
    (net (code "35") (name "Net-(IC1-TXD)") (class "Default")
      (node (ref "IC1") (pin "26") (pinfunction "TXD_26") (pintype "output"))
      (node (ref "R3") (pin "2") (pinfunction "2_2") (pintype "passive"))
    )
    (net (code "36") (name "Net-(IC1-VBUS)") (class "Default")
      (node (ref "IC1") (pin "8") (pinfunction "VBUS_8") (pintype "input"))
      (node (ref "R43") (pin "1") (pinfunction "1_1") (pintype "passive"))
      (node (ref "R44") (pin "2") (pinfunction "2_2") (pintype "passive"))
    )
    (net (code "37") (name "Net-(IC1-~{RST})") (class "Default")
      (node (ref "IC1") (pin "9") (pinfunction "~{RST}_9") (pintype "bidirectional"))
      (node (ref "R42") (pin "2") (pinfunction "2_2") (pintype "passive"))
    )
    (net (code "38") (name "Net-(IC2-B)") (class "Default")
      (node (ref "IC2") (pin "4") (pinfunction "B_4") (pintype "bidirectional"))
      (node (ref "R8") (pin "1") (pinfunction "1_1") (pintype "passive"))
    )
    (net (code "39") (name "Net-(J1-Pad3)") (class "Default")
      (node (ref "J1") (pin "3") (pinfunction "3_3") (pintype "passive"))
      (node (ref "R41") (pin "1") (pinfunction "1_1") (pintype "passive"))
    )
    (net (code "40") (name "Net-(JTAG1-Pad2)") (class "Default")
      (node (ref "JTAG1") (pin "2") (pinfunction "2_2") (pintype "passive"))
      (node (ref "R24") (pin "1") (pinfunction "1_1") (pintype "passive"))
    )
    (net (code "41") (name "Net-(JTAG1-Pad4)") (class "Default")
      (node (ref "JTAG1") (pin "4") (pinfunction "4_4") (pintype "passive"))
      (node (ref "R13") (pin "1") (pinfunction "1_1") (pintype "passive"))
    )
    (net (code "42") (name "Net-(JTAG1-Pad6)") (class "Default")
      (node (ref "JTAG1") (pin "6") (pinfunction "6_6") (pintype "passive"))
      (node (ref "R12") (pin "1") (pinfunction "1_1") (pintype "passive"))
    )
    (net (code "43") (name "Net-(JTAG1-Pad8)") (class "Default")
      (node (ref "JTAG1") (pin "8") (pinfunction "8_8") (pintype "passive"))
      (node (ref "R10") (pin "1") (pinfunction "1_1") (pintype "passive"))
    )
    (net (code "44") (name "Net-(L2-1)") (class "Default")
      (node (ref "C1") (pin "2") (pinfunction "2_2") (pintype "passive"))
      (node (ref "L2") (pin "P$1") (pinfunction "1_P$1") (pintype "passive"))
      (node (ref "U4") (pin "2") (pinfunction "SW_2") (pintype "bidirectional"))
    )
    (net (code "45") (name "Net-(LED1-A_B)") (class "Default")
      (node (ref "LED1") (pin "6") (pinfunction "A_B_6") (pintype "passive"))
      (node (ref "R19") (pin "1") (pinfunction "1_1") (pintype "passive"))
    )
    (net (code "46") (name "Net-(LED1-A_G)") (class "Default")
      (node (ref "LED1") (pin "5") (pinfunction "A_G_5") (pintype "passive"))
      (node (ref "R11") (pin "1") (pinfunction "1_1") (pintype "passive"))
    )
    (net (code "47") (name "Net-(LED1-A_R)") (class "Default")
      (node (ref "LED1") (pin "4") (pinfunction "A_R_4") (pintype "passive"))
      (node (ref "R14") (pin "1") (pinfunction "1_1") (pintype "passive"))
    )
    (net (code "48") (name "Net-(Q3-D)") (class "Default")
      (node (ref "J4") (pin "1") (pinfunction "1_1") (pintype "passive"))
      (node (ref "Q3") (pin "3") (pinfunction "D_3") (pintype "bidirectional"))
    )
    (net (code "49") (name "Net-(T1-B)") (class "Default")
      (node (ref "R2") (pin "1") (pinfunction "1_1") (pintype "passive"))
      (node (ref "T1") (pin "1") (pinfunction "B_1") (pintype "passive"))
    )
    (net (code "50") (name "Net-(T2-B)") (class "Default")
      (node (ref "R1") (pin "1") (pinfunction "1_1") (pintype "passive"))
      (node (ref "T2") (pin "1") (pinfunction "B_1") (pintype "passive"))
    )
    (net (code "51") (name "Net-(U2-IO4)") (class "Default")
      (node (ref "R35") (pin "1") (pinfunction "1_1") (pintype "passive"))
      (node (ref "U2") (pin "26") (pinfunction "IO4_26") (pintype "bidirectional"))
    )
    (net (code "52") (name "Net-(U2-IO17)") (class "Default")
      (node (ref "R27") (pin "1") (pinfunction "1_1") (pintype "passive"))
      (node (ref "U2") (pin "28") (pinfunction "IO17_28") (pintype "bidirectional"))
    )
    (net (code "53") (name "Net-(U2-IO21)") (class "Default")
      (node (ref "R32") (pin "1") (pinfunction "1_1") (pintype "passive"))
      (node (ref "U2") (pin "33") (pinfunction "IO21_33") (pintype "bidirectional"))
    )
    (net (code "54") (name "Net-(U2-IO22)") (class "Default")
      (node (ref "R33") (pin "1") (pinfunction "1_1") (pintype "passive"))
      (node (ref "U2") (pin "36") (pinfunction "IO22_36") (pintype "bidirectional"))
    )
    (net (code "55") (name "Net-(U4-EN)") (class "Default")
      (node (ref "R22") (pin "1") (pinfunction "1_1") (pintype "passive"))
      (node (ref "TP1") (pin "TP") (pinfunction "TP_TP") (pintype "input"))
      (node (ref "U4") (pin "5") (pinfunction "EN_5") (pintype "bidirectional"))
    )
    (net (code "56") (name "Net-(U4-VBST)") (class "Default")
      (node (ref "R16") (pin "2") (pinfunction "2_2") (pintype "passive"))
      (node (ref "U4") (pin "6") (pinfunction "VBST_6") (pintype "bidirectional"))
    )
    (net (code "57") (name "Net-(U4-VFB)") (class "Default")
      (node (ref "R28") (pin "1") (pinfunction "1_1") (pintype "passive"))
      (node (ref "R29") (pin "1") (pinfunction "1_1") (pintype "passive"))
      (node (ref "R30") (pin "1") (pinfunction "1_1") (pintype "passive"))
      (node (ref "U4") (pin "4") (pinfunction "VFB_4") (pintype "bidirectional"))
    )
    (net (code "58") (name "RTS") (class "Default")
      (node (ref "IC1") (pin "24") (pinfunction "RTS_24") (pintype "output"))
      (node (ref "R2") (pin "2") (pinfunction "2_2") (pintype "passive"))
      (node (ref "T2") (pin "2") (pinfunction "E_2") (pintype "passive"))
    )
    (net (code "59") (name "RXD0") (class "Default")
      (node (ref "J3") (pin "5") (pinfunction "5_5") (pintype "passive"))
      (node (ref "R3") (pin "1") (pinfunction "1_1") (pintype "passive"))
      (node (ref "U2") (pin "34") (pinfunction "RXD_34") (pintype "bidirectional"))
    )
    (net (code "60") (name "SCL") (class "Default")
      (node (ref "J2") (pin "3") (pinfunction "3_3") (pintype "passive"))
      (node (ref "R39") (pin "2") (pinfunction "2_2") (pintype "passive"))
      (node (ref "U2") (pin "8") (pinfunction "XTAL_P/IO32_8") (pintype "bidirectional"))
    )
    (net (code "61") (name "SDA") (class "Default")
      (node (ref "J2") (pin "4") (pinfunction "4_4") (pintype "passive"))
      (node (ref "R38") (pin "2") (pinfunction "2_2") (pintype "passive"))
      (node (ref "U2") (pin "9") (pinfunction "XTAL_N/IO33_9") (pintype "bidirectional"))
    )
    (net (code "62") (name "TXD0") (class "Default")
      (node (ref "J3") (pin "3") (pinfunction "3_3") (pintype "passive"))
      (node (ref "R4") (pin "1") (pinfunction "1_1") (pintype "passive"))
      (node (ref "U2") (pin "35") (pinfunction "TXD_35") (pintype "bidirectional"))
    )
    (net (code "63") (name "VGI") (class "Default")
      (node (ref "Q2") (pin "1") (pinfunction "G_1") (pintype "passive"))
      (node (ref "R53") (pin "1") (pinfunction "1_1") (pintype "passive"))
      (node (ref "R54") (pin "2") (pinfunction "2_2") (pintype "passive"))
    )
    (net (code "64") (name "VIN") (class "Default")
      (node (ref "C14") (pin "1") (pinfunction "1_1") (pintype "passive"))
      (node (ref "C15") (pin "1") (pinfunction "1_1") (pintype "passive"))
      (node (ref "C17") (pin "1") (pinfunction "1_1") (pintype "passive"))
      (node (ref "C7") (pin "2") (pinfunction "2_2") (pintype "passive"))
      (node (ref "D4") (pin "3") (pinfunction "3_3") (pintype "passive"))
      (node (ref "FB1") (pin "2") (pinfunction "P$2_2") (pintype "passive"))
      (node (ref "FB4") (pin "1") (pinfunction "P$1_1") (pintype "passive"))
      (node (ref "IC2") (pin "6") (pinfunction "VCC(B)_6") (pintype "bidirectional"))
      (node (ref "J6") (pin "P4A") (pinfunction "1_P4A") (pintype "passive"))
      (node (ref "J6") (pin "P4B") (pinfunction "1_P4B") (pintype "passive"))
      (node (ref "X2") (pin "1") (pinfunction "KL_1") (pintype "passive"))
    )
    (net (code "65") (name "VIN_PROTECTED") (class "Default")
      (node (ref "C6") (pin "1") (pinfunction "1_1") (pintype "passive"))
      (node (ref "C8") (pin "1") (pinfunction "1_1") (pintype "passive"))
      (node (ref "C9") (pin "1") (pinfunction "1_1") (pintype "passive"))
      (node (ref "J4") (pin "2") (pinfunction "2_2") (pintype "passive"))
      (node (ref "Q2") (pin "2") (pinfunction "S_2") (pintype "passive"))
      (node (ref "R22") (pin "2") (pinfunction "2_2") (pintype "passive"))
      (node (ref "U4") (pin "3") (pinfunction "VIN_3") (pintype "bidirectional"))
    )
    (net (code "66") (name "VSPI_MISO") (class "Default")
      (node (ref "R31") (pin "1") (pinfunction "1_1") (pintype "passive"))
      (node (ref "U2") (pin "31") (pinfunction "MISO_V/IO19_31") (pintype "bidirectional"))
    )
    (net (code "67") (name "VSPI_MOSI") (class "Default")
      (node (ref "R17") (pin "1") (pinfunction "1_1") (pintype "passive"))
      (node (ref "U2") (pin "30") (pinfunction "SCK_V/IO18_30") (pintype "bidirectional"))
    )
    (net (code "68") (name "VSPI_SCK") (class "Default")
      (node (ref "R34") (pin "1") (pinfunction "1_1") (pintype "passive"))
      (node (ref "U2") (pin "29") (pinfunction "CS0_V/IO5_29") (pintype "bidirectional"))
    )
    (net (code "69") (name "V_USB") (class "Default")
      (node (ref "C5") (pin "1") (pinfunction "1_1") (pintype "passive"))
      (node (ref "D1") (pin "1") (pinfunction "1_1") (pintype "passive"))
      (node (ref "D2") (pin "1") (pinfunction "1_1") (pintype "passive"))
      (node (ref "FB1") (pin "1") (pinfunction "P$1_1") (pintype "passive"))
      (node (ref "J5") (pin "VBUS") (pinfunction "VBUS_VBUS") (pintype "power_in"))
      (node (ref "R43") (pin "2") (pinfunction "2_2") (pintype "passive"))
    )
    (net (code "70") (name "unconnected-(IC1-CTS-Pad23)") (class "Default")
      (node (ref "IC1") (pin "23") (pinfunction "CTS_23") (pintype "input"))
    )
    (net (code "71") (name "unconnected-(IC1-DCD-Pad1)") (class "Default")
      (node (ref "IC1") (pin "1") (pinfunction "DCD_1") (pintype "input"))
    )
    (net (code "72") (name "unconnected-(IC1-DSR-Pad27)") (class "Default")
      (node (ref "IC1") (pin "27") (pinfunction "DSR_27") (pintype "input"))
    )
    (net (code "73") (name "unconnected-(IC1-RI-Pad2)") (class "Default")
      (node (ref "IC1") (pin "2") (pinfunction "RI_2") (pintype "input"))
    )
    (net (code "74") (name "unconnected-(IC1-SUSPEND-Pad12)") (class "Default")
      (node (ref "IC1") (pin "12") (pinfunction "SUSPEND_12") (pintype "output"))
    )
    (net (code "75") (name "unconnected-(J5-PadID)") (class "Default")
      (node (ref "J5") (pin "ID") (pinfunction "ID_ID") (pintype "bidirectional"))
    )
    (net (code "76") (name "unconnected-(U2-IO2-Pad24)") (class "Default")
      (node (ref "U2") (pin "24") (pinfunction "IO2_24") (pintype "bidirectional"))
    )
    (net (code "77") (name "unconnected-(U2-NC-Pad32)") (class "Default")
      (node (ref "U2") (pin "32") (pinfunction "NC_32") (pintype "bidirectional"))
    )
    (net (code "78") (name "unconnected-(U2-SCK{slash}IO6-Pad20)") (class "Default")
      (node (ref "U2") (pin "20") (pinfunction "SCK/IO6_20") (pintype "bidirectional"))
    )
    (net (code "79") (name "unconnected-(U2-SCS{slash}IO11-Pad19)") (class "Default")
      (node (ref "U2") (pin "19") (pinfunction "SCS/IO11_19") (pintype "bidirectional"))
    )
    (net (code "80") (name "unconnected-(U2-SDI{slash}IO8-Pad22)") (class "Default")
      (node (ref "U2") (pin "22") (pinfunction "SDI/IO8_22") (pintype "bidirectional"))
    )
    (net (code "81") (name "unconnected-(U2-SDO{slash}IO7-Pad21)") (class "Default")
      (node (ref "U2") (pin "21") (pinfunction "SDO/IO7_21") (pintype "bidirectional"))
    )
    (net (code "82") (name "unconnected-(U2-SENSOR_VN{slash}I39-Pad5)") (class "Default")
      (node (ref "U2") (pin "5") (pinfunction "SENSOR_VN/I39_5") (pintype "bidirectional"))
    )
    (net (code "83") (name "unconnected-(U2-SHD{slash}IO9-Pad17)") (class "Default")
      (node (ref "U2") (pin "17") (pinfunction "SHD/IO9_17") (pintype "bidirectional"))
    )
    (net (code "84") (name "unconnected-(U2-SWP{slash}IO10-Pad18)") (class "Default")
      (node (ref "U2") (pin "18") (pinfunction "SWP/IO10_18") (pintype "bidirectional"))
    )
  )
)
